# Filters.net
KiCad netlist of a schematic drawn in Altium Designer
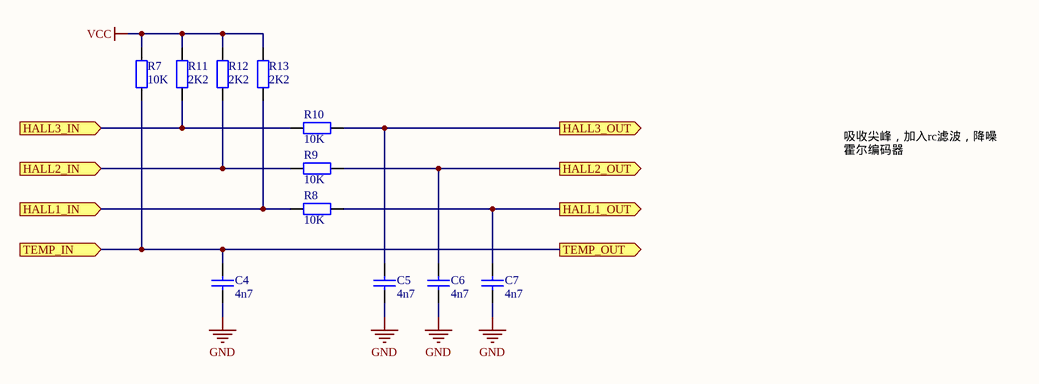
[diagram p0: Filters.SchDoc]

(export (version "E")
  (design (tool "Eeschema 10.0.6"))
  (components
    (comp (ref "C4")
      (value "4n7")
      (footprint "0402")
      (description "Capacitor")
      (fields (field (name "Comment") "CAP") (field (name "PUBLISHER") "Altium Limited"))
      (libsource (lib "TAOXUN") (part "CAP"))
    )
    (comp (ref "C5")
      (value "4n7")
      (footprint "0402")
      (description "Capacitor")
      (fields (field (name "Comment") "CAP") (field (name "PUBLISHER") "Altium Limited"))
      (libsource (lib "TAOXUN") (part "CAP"))
    )
    (comp (ref "C6")
      (value "4n7")
      (footprint "0402")
      (description "Capacitor")
      (fields (field (name "Comment") "CAP") (field (name "PUBLISHER") "Altium Limited"))
      (libsource (lib "TAOXUN") (part "CAP"))
    )
    (comp (ref "C7")
      (value "4n7")
      (footprint "0402")
      (description "Capacitor")
      (fields (field (name "Comment") "CAP") (field (name "PUBLISHER") "Altium Limited"))
      (libsource (lib "TAOXUN") (part "CAP"))
    )
    (comp (ref "R7")
      (value "10K")
      (footprint "0402")
      (description "贴片电阻")
      (fields (field (name "Comment") "Res1") (field (name "PUBLISHER") "Altium Limited"))
      (libsource (lib "") (part "Res1_1"))
    )
    (comp (ref "R8")
      (value "10K")
      (footprint "0402")
      (description "贴片电阻")
      (fields (field (name "Comment") "Res1") (field (name "PUBLISHER") "Altium Limited"))
      (libsource (lib "TAOXUN") (part "Res1"))
    )
    (comp (ref "R9")
      (value "10K")
      (footprint "0402")
      (description "贴片电阻")
      (fields (field (name "Comment") "Res1") (field (name "PUBLISHER") "Altium Limited"))
      (libsource (lib "TAOXUN") (part "Res1"))
    )
    (comp (ref "R10")
      (value "10K")
      (footprint "0402")
      (description "贴片电阻")
      (fields (field (name "Comment") "Res1") (field (name "PUBLISHER") "Altium Limited"))
      (libsource (lib "TAOXUN") (part "Res1"))
    )
    (comp (ref "R11")
      (value "2K2")
      (footprint "0402")
      (description "贴片电阻")
      (fields (field (name "Comment") "Res1") (field (name "PUBLISHER") "Altium Limited"))
      (libsource (lib "") (part "Res1_1"))
    )
    (comp (ref "R12")
      (value "2K2")
      (footprint "0402")
      (description "贴片电阻")
      (fields (field (name "Comment") "Res1") (field (name "PUBLISHER") "Altium Limited"))
      (libsource (lib "") (part "Res1_1"))
    )
    (comp (ref "R13")
      (value "2K2")
      (footprint "0402")
      (description "贴片电阻")
      (fields (field (name "Comment") "Res1") (field (name "PUBLISHER") "Altium Limited"))
      (libsource (lib "") (part "Res1_1"))
    )
  )
  (nets
    (net (code "1") (name "/HALL1_IN") (class "Default")
      (node (ref "R13") (pin "2") (pinfunction "2_2") (pintype "passive"))
      (node (ref "R8") (pin "1") (pinfunction "1_1") (pintype "passive"))
    )
    (net (code "2") (name "/HALL1_OUT") (class "Default")
      (node (ref "C7") (pin "2") (pinfunction "2_2") (pintype "passive"))
      (node (ref "R8") (pin "2") (pinfunction "2_2") (pintype "passive"))
    )
    (net (code "3") (name "/HALL2_IN") (class "Default")
      (node (ref "R12") (pin "2") (pinfunction "2_2") (pintype "passive"))
      (node (ref "R9") (pin "1") (pinfunction "1_1") (pintype "passive"))
    )
    (net (code "4") (name "/HALL2_OUT") (class "Default")
      (node (ref "C6") (pin "2") (pinfunction "2_2") (pintype "passive"))
      (node (ref "R9") (pin "2") (pinfunction "2_2") (pintype "passive"))
    )
    (net (code "5") (name "/HALL3_IN") (class "Default")
      (node (ref "R10") (pin "1") (pinfunction "1_1") (pintype "passive"))
      (node (ref "R11") (pin "2") (pinfunction "2_2") (pintype "passive"))
    )
    (net (code "6") (name "/HALL3_OUT") (class "Default")
      (node (ref "C5") (pin "2") (pinfunction "2_2") (pintype "passive"))
      (node (ref "R10") (pin "2") (pinfunction "2_2") (pintype "passive"))
    )
    (net (code "7") (name "/TEMP_IN") (class "Default")
      (node (ref "C4") (pin "2") (pinfunction "2_2") (pintype "passive"))
      (node (ref "R7") (pin "2") (pinfunction "2_2") (pintype "passive"))
    )
    (net (code "8") (name "GND") (class "Default")
      (node (ref "C4") (pin "1") (pinfunction "1_1") (pintype "passive"))
      (node (ref "C5") (pin "1") (pinfunction "1_1") (pintype "passive"))
      (node (ref "C6") (pin "1") (pinfunction "1_1") (pintype "passive"))
      (node (ref "C7") (pin "1") (pinfunction "1_1") (pintype "passive"))
    )
    (net (code "9") (name "VCC") (class "Default")
      (node (ref "R11") (pin "1") (pinfunction "1_1") (pintype "passive"))
      (node (ref "R12") (pin "1") (pinfunction "1_1") (pintype "passive"))
      (node (ref "R13") (pin "1") (pinfunction "1_1") (pintype "passive"))
      (node (ref "R7") (pin "1") (pinfunction "1_1") (pintype "passive"))
    )
  )
)
